# Radio.net
KiCad netlist of a schematic drawn in Altium Designer
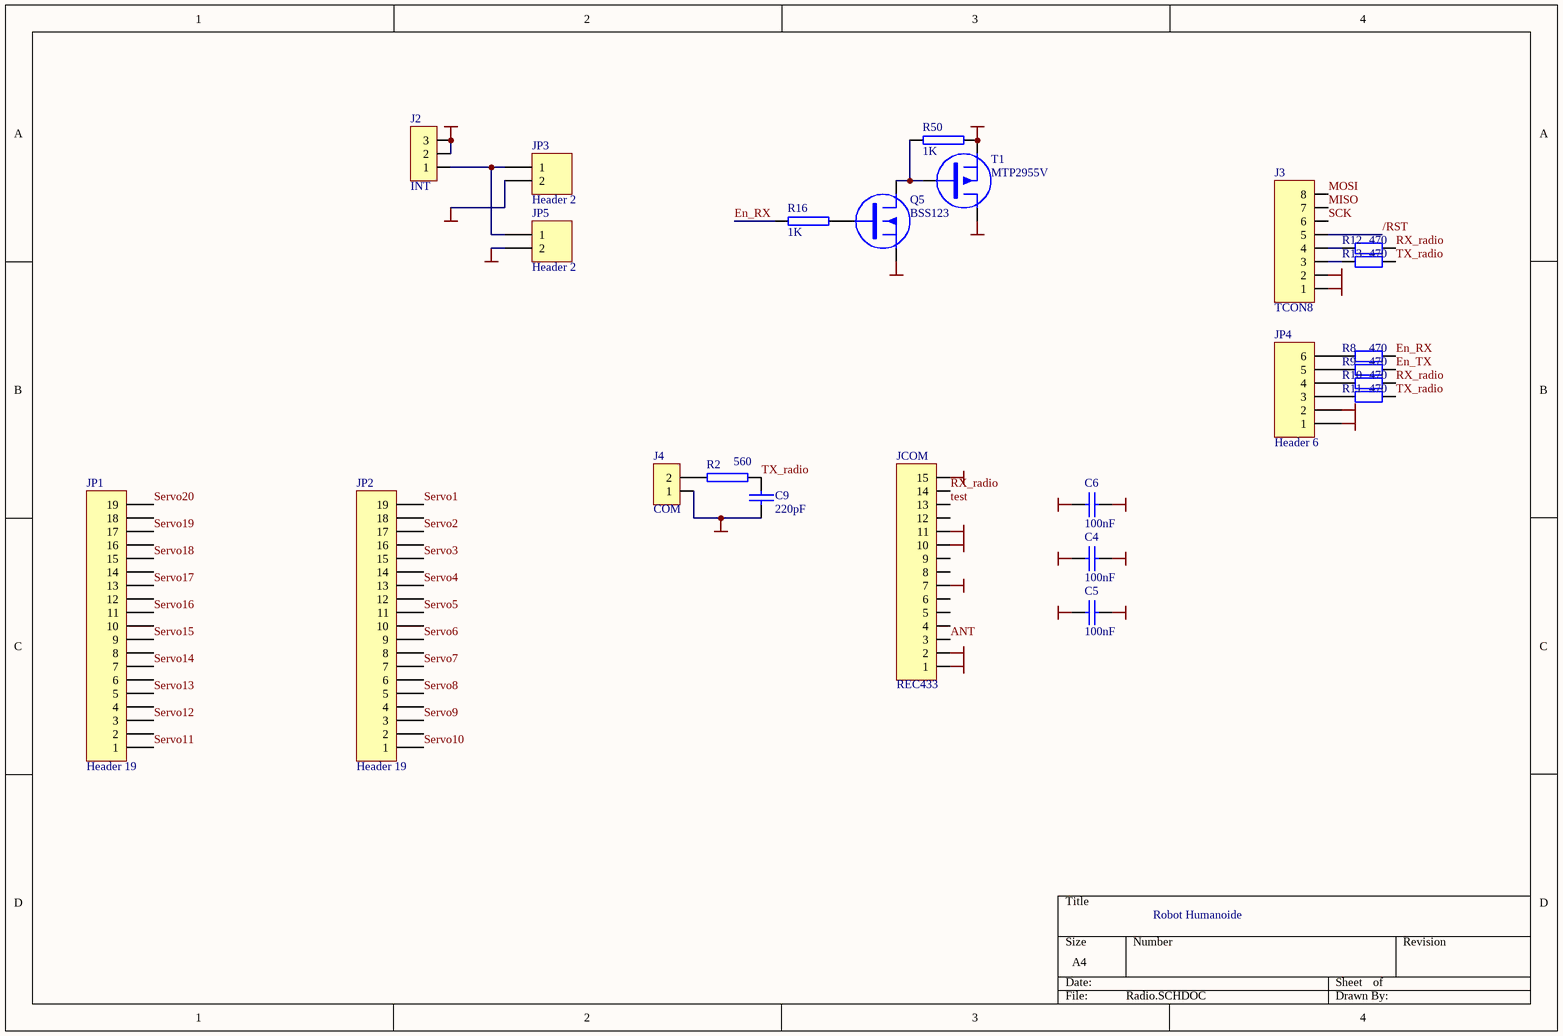
[diagram p0: Radio.SCHDOC]

(export (version "E")
  (design (tool "Eeschema 10.0.6"))
  (components
    (comp (ref "C4")
      (value "100nF")
      (footprint "0805")
      (fields
        (field (name "MANUFACTURER") "Generic Components")
        (field (name "PUBLISHER") "Altium Hobart Technology Centre")
      )
      (libsource (lib "*") (part "CAP"))
    )
    (comp (ref "C5")
      (value "100nF")
      (footprint "0805")
      (fields
        (field (name "MANUFACTURER") "Generic Components")
        (field (name "PUBLISHER") "Altium Hobart Technology Centre")
      )
      (libsource (lib "*") (part "CAP"))
    )
    (comp (ref "C6")
      (value "100nF")
      (footprint "0805")
      (fields
        (field (name "MANUFACTURER") "Generic Components")
        (field (name "PUBLISHER") "Altium Hobart Technology Centre")
      )
      (libsource (lib "*") (part "CAP"))
    )
    (comp (ref "C9")
      (value "220pF")
      (footprint "0805")
      (fields
        (field (name "MANUFACTURER") "Generic Components")
        (field (name "PUBLISHER") "Altium Hobart Technology Centre")
      )
      (libsource (lib "*") (part "CAP"))
    )
    (comp (ref "J2") (value "INT") (footprint "TSIP3") (libsource (lib "*") (part "TCON3")))
    (comp (ref "J3") (value "TCON8") (footprint "TSIP8") (libsource (lib "ROB04") (part "TCON8")))
    (comp (ref "J4") (value "COM") (footprint "CON2") (libsource (lib "*") (part "CON2")))
    (comp (ref "JCOM") (value "REC433") (footprint "TSIP15") (libsource (lib "*") (part "CON15")))
    (comp (ref "JP1")
      (value "Header 19")
      (footprint "HDR1X19")
      (description "Header, 19-Pin")
      (fields (field (name "PUBLISHER") "Altium Limited"))
      (libsource (lib "Miscellaneous Connectors") (part "Header 19"))
    )
    (comp (ref "JP2")
      (value "Header 19")
      (footprint "HDR1X19")
      (description "Header, 19-Pin")
      (fields (field (name "PUBLISHER") "Altium Limited"))
      (libsource (lib "Miscellaneous Connectors") (part "Header 19"))
    )
    (comp (ref "JP3")
      (value "Header 2")
      (footprint "HDR1X2")
      (description "Header, 2-Pin")
      (fields (field (name "PUBLISHER") "Altium Limited"))
      (libsource (lib "Miscellaneous Connectors") (part "Header 2"))
    )
    (comp (ref "JP4")
      (value "Header 6")
      (footprint "TSIP6")
      (description "Header, 6-Pin")
      (fields (field (name "PUBLISHER") "Altium Limited"))
      (libsource (lib "Miscellaneous Connectors") (part "Header 6"))
    )
    (comp (ref "JP5")
      (value "Header 2")
      (footprint "HDR1X2")
      (description "Header, 2-Pin")
      (fields (field (name "PUBLISHER") "Altium Limited"))
      (libsource (lib "Miscellaneous Connectors") (part "Header 2"))
    )
    (comp (ref "Q5") (value "BSS123") (footprint "SOT-23") (libsource (lib "*") (part "BSS123")))
    (comp (ref "R2")
      (value "560")
      (footprint "0805")
      (fields (field (name "PUBLISHER") "*"))
      (libsource (lib "*") (part "RES2"))
    )
    (comp (ref "R8")
      (value "470")
      (footprint "0805")
      (description "Resistor")
      (fields (field (name "Comment") "Res2") (field (name "PUBLISHER") "Altium Limited"))
      (libsource (lib "Miscellaneous Devices") (part "Res2"))
    )
    (comp (ref "R9")
      (value "470")
      (footprint "0805")
      (description "Resistor")
      (fields (field (name "Comment") "Res2") (field (name "PUBLISHER") "Altium Limited"))
      (libsource (lib "Miscellaneous Devices") (part "Res2"))
    )
    (comp (ref "R10")
      (value "470")
      (footprint "0805")
      (description "Resistor")
      (fields (field (name "Comment") "Res2") (field (name "PUBLISHER") "Altium Limited"))
      (libsource (lib "Miscellaneous Devices") (part "Res2"))
    )
    (comp (ref "R11")
      (value "470")
      (footprint "0805")
      (description "Resistor")
      (fields (field (name "Comment") "Res2") (field (name "PUBLISHER") "Altium Limited"))
      (libsource (lib "Miscellaneous Devices") (part "Res2"))
    )
    (comp (ref "R12")
      (value "470")
      (footprint "0805")
      (description "Resistor")
      (fields (field (name "Comment") "Res2") (field (name "PUBLISHER") "Altium Limited"))
      (libsource (lib "Miscellaneous Devices") (part "Res2"))
    )
    (comp (ref "R13")
      (value "470")
      (footprint "0805")
      (description "Resistor")
      (fields (field (name "Comment") "Res2") (field (name "PUBLISHER") "Altium Limited"))
      (libsource (lib "Miscellaneous Devices") (part "Res2"))
    )
    (comp (ref "R16") (value "1K") (footprint "0805") (libsource (lib "*") (part "TRESIST")))
    (comp (ref "R50") (value "1K") (footprint "0805") (libsource (lib "*") (part "TRESIST")))
    (comp (ref "T1") (value "MTP2955V") (footprint "TTO220C") (libsource (lib "*") (part "MTP2955V")))
  )
  (nets
    (net (code "1") (name "/ANT") (class "Default")
      (node (ref "JCOM") (pin "3") (pinfunction "3_3") (pintype "passive"))
    )
    (net (code "2") (name "/En_RX") (class "Default")
      (node (ref "R16") (pin "1") (pintype "passive"))
      (node (ref "R8") (pin "2") (pinfunction "2_2") (pintype "passive"))
    )
    (net (code "3") (name "/En_TX") (class "Default")
      (node (ref "R9") (pin "2") (pinfunction "2_2") (pintype "passive"))
    )
    (net (code "4") (name "/MISO") (class "Default")
      (node (ref "J3") (pin "7") (pinfunction "7_7") (pintype "passive"))
    )
    (net (code "5") (name "/MOSI") (class "Default")
      (node (ref "J3") (pin "8") (pinfunction "8_8") (pintype "passive"))
    )
    (net (code "6") (name "/RX_radio") (class "Default")
      (node (ref "JCOM") (pin "14") (pinfunction "14_14") (pintype "passive"))
      (node (ref "R10") (pin "2") (pinfunction "2_2") (pintype "passive"))
      (node (ref "R12") (pin "2") (pinfunction "2_2") (pintype "passive"))
    )
    (net (code "7") (name "/SCK") (class "Default")
      (node (ref "J3") (pin "6") (pinfunction "6_6") (pintype "passive"))
    )
    (net (code "8") (name "/Servo1") (class "Default")
      (node (ref "JP2") (pin "19") (pinfunction "19_19") (pintype "passive"))
    )
    (net (code "9") (name "/Servo2") (class "Default")
      (node (ref "JP2") (pin "17") (pinfunction "17_17") (pintype "passive"))
    )
    (net (code "10") (name "/Servo3") (class "Default")
      (node (ref "JP2") (pin "15") (pinfunction "15_15") (pintype "passive"))
    )
    (net (code "11") (name "/Servo4") (class "Default")
      (node (ref "JP2") (pin "13") (pinfunction "13_13") (pintype "passive"))
    )
    (net (code "12") (name "/Servo5") (class "Default")
      (node (ref "JP2") (pin "11") (pinfunction "11_11") (pintype "passive"))
    )
    (net (code "13") (name "/Servo6") (class "Default")
      (node (ref "JP2") (pin "9") (pinfunction "9_9") (pintype "passive"))
    )
    (net (code "14") (name "/Servo7") (class "Default")
      (node (ref "JP2") (pin "7") (pinfunction "7_7") (pintype "passive"))
    )
    (net (code "15") (name "/Servo8") (class "Default")
      (node (ref "JP2") (pin "5") (pinfunction "5_5") (pintype "passive"))
    )
    (net (code "16") (name "/Servo9") (class "Default")
      (node (ref "JP2") (pin "3") (pinfunction "3_3") (pintype "passive"))
    )
    (net (code "17") (name "/Servo10") (class "Default")
      (node (ref "JP2") (pin "1") (pinfunction "1_1") (pintype "passive"))
    )
    (net (code "18") (name "/Servo11") (class "Default")
      (node (ref "JP1") (pin "1") (pinfunction "1_1") (pintype "passive"))
    )
    (net (code "19") (name "/Servo12") (class "Default")
      (node (ref "JP1") (pin "3") (pinfunction "3_3") (pintype "passive"))
    )
    (net (code "20") (name "/Servo13") (class "Default")
      (node (ref "JP1") (pin "5") (pinfunction "5_5") (pintype "passive"))
    )
    (net (code "21") (name "/Servo14") (class "Default")
      (node (ref "JP1") (pin "7") (pinfunction "7_7") (pintype "passive"))
    )
    (net (code "22") (name "/Servo15") (class "Default")
      (node (ref "JP1") (pin "9") (pinfunction "9_9") (pintype "passive"))
    )
    (net (code "23") (name "/Servo16") (class "Default")
      (node (ref "JP1") (pin "11") (pinfunction "11_11") (pintype "passive"))
    )
    (net (code "24") (name "/Servo17") (class "Default")
      (node (ref "JP1") (pin "13") (pinfunction "13_13") (pintype "passive"))
    )
    (net (code "25") (name "/Servo18") (class "Default")
      (node (ref "JP1") (pin "15") (pinfunction "15_15") (pintype "passive"))
    )
    (net (code "26") (name "/Servo19") (class "Default")
      (node (ref "JP1") (pin "17") (pinfunction "17_17") (pintype "passive"))
    )
    (net (code "27") (name "/Servo20") (class "Default")
      (node (ref "JP1") (pin "19") (pinfunction "19_19") (pintype "passive"))
    )
    (net (code "28") (name "/TX_radio") (class "Default")
      (node (ref "C9") (pin "2") (pintype "passive"))
      (node (ref "R11") (pin "2") (pinfunction "2_2") (pintype "passive"))
      (node (ref "R13") (pin "2") (pinfunction "2_2") (pintype "passive"))
      (node (ref "R2") (pin "2") (pintype "passive"))
    )
    (net (code "29") (name "/test") (class "Default")
      (node (ref "JCOM") (pin "13") (pinfunction "13_13") (pintype "passive"))
    )
    (net (code "30") (name "/{slash}RST") (class "Default")
      (node (ref "J3") (pin "5") (pinfunction "5_5") (pintype "passive"))
    )
    (net (code "31") (name "5V") (class "Default")
      (node (ref "C4") (pin "2") (pintype "passive"))
      (node (ref "C5") (pin "2") (pintype "passive"))
      (node (ref "C6") (pin "2") (pintype "passive"))
      (node (ref "J3") (pin "1") (pinfunction "1_1") (pintype "passive"))
      (node (ref "JCOM") (pin "1") (pinfunction "1_1") (pintype "passive"))
      (node (ref "JCOM") (pin "10") (pinfunction "10_10") (pintype "passive"))
      (node (ref "JCOM") (pin "15") (pinfunction "15_15") (pintype "passive"))
      (node (ref "JP4") (pin "1") (pinfunction "1_1") (pintype "passive"))
      (node (ref "T1") (pin "2") (pinfunction "C_2") (pintype "passive"))
    )
    (net (code "32") (name "GND") (class "Default")
      (node (ref "C4") (pin "1") (pintype "passive"))
      (node (ref "C5") (pin "1") (pintype "passive"))
      (node (ref "C6") (pin "1") (pintype "passive"))
      (node (ref "C9") (pin "1") (pintype "passive"))
      (node (ref "J3") (pin "2") (pinfunction "2_2") (pintype "passive"))
      (node (ref "J4") (pin "1") (pinfunction "1_1") (pintype "passive"))
      (node (ref "JCOM") (pin "11") (pinfunction "11_11") (pintype "passive"))
      (node (ref "JCOM") (pin "2") (pinfunction "2_2") (pintype "passive"))
      (node (ref "JCOM") (pin "7") (pinfunction "7_7") (pintype "passive"))
      (node (ref "JP3") (pin "2") (pinfunction "2_2") (pintype "passive"))
      (node (ref "JP4") (pin "2") (pinfunction "2_2") (pintype "passive"))
      (node (ref "JP5") (pin "2") (pinfunction "2_2") (pintype "passive"))
      (node (ref "Q5") (pin "2") (pinfunction "C_2") (pintype "passive"))
    )
    (net (code "33") (name "Net-(J2-Pad1)") (class "Default")
      (node (ref "J2") (pin "1") (pinfunction "1_1") (pintype "passive"))
      (node (ref "JP3") (pin "1") (pinfunction "1_1") (pintype "passive"))
      (node (ref "JP5") (pin "1") (pinfunction "1_1") (pintype "passive"))
    )
    (net (code "34") (name "Net-(J3-Pad3)") (class "Default")
      (node (ref "J3") (pin "3") (pinfunction "3_3") (pintype "passive"))
      (node (ref "R13") (pin "1") (pinfunction "1_1") (pintype "passive"))
    )
    (net (code "35") (name "Net-(J3-Pad4)") (class "Default")
      (node (ref "J3") (pin "4") (pinfunction "4_4") (pintype "passive"))
      (node (ref "R12") (pin "1") (pinfunction "1_1") (pintype "passive"))
    )
    (net (code "36") (name "Net-(J4-Pad2)") (class "Default")
      (node (ref "J4") (pin "2") (pinfunction "2_2") (pintype "passive"))
      (node (ref "R2") (pin "1") (pintype "passive"))
    )
    (net (code "37") (name "Net-(JP4-Pad3)") (class "Default")
      (node (ref "JP4") (pin "3") (pinfunction "3_3") (pintype "passive"))
      (node (ref "R11") (pin "1") (pinfunction "1_1") (pintype "passive"))
    )
    (net (code "38") (name "Net-(JP4-Pad4)") (class "Default")
      (node (ref "JP4") (pin "4") (pinfunction "4_4") (pintype "passive"))
      (node (ref "R10") (pin "1") (pinfunction "1_1") (pintype "passive"))
    )
    (net (code "39") (name "Net-(JP4-Pad5)") (class "Default")
      (node (ref "JP4") (pin "5") (pinfunction "5_5") (pintype "passive"))
      (node (ref "R9") (pin "1") (pinfunction "1_1") (pintype "passive"))
    )
    (net (code "40") (name "Net-(JP4-Pad6)") (class "Default")
      (node (ref "JP4") (pin "6") (pinfunction "6_6") (pintype "passive"))
      (node (ref "R8") (pin "1") (pinfunction "1_1") (pintype "passive"))
    )
    (net (code "41") (name "Net-(Q5-B)") (class "Default")
      (node (ref "Q5") (pin "1") (pinfunction "B_1") (pintype "passive"))
      (node (ref "R16") (pin "2") (pintype "passive"))
    )
    (net (code "42") (name "Net-(Q5-E)") (class "Default")
      (node (ref "Q5") (pin "3") (pinfunction "E_3") (pintype "passive"))
      (node (ref "R50") (pin "1") (pintype "passive"))
      (node (ref "T1") (pin "1") (pinfunction "B_1") (pintype "passive"))
    )
    (net (code "43") (name "VCC") (class "Default")
      (node (ref "J2") (pin "2") (pinfunction "2_2") (pintype "passive"))
      (node (ref "J2") (pin "3") (pinfunction "3_3") (pintype "passive"))
      (node (ref "R50") (pin "2") (pintype "passive"))
      (node (ref "T1") (pin "3") (pinfunction "E_3") (pintype "passive"))
    )
    (net (code "44") (name "unconnected-(JCOM-Pad4)") (class "Default")
      (node (ref "JCOM") (pin "4") (pinfunction "4_4") (pintype "passive"))
    )
    (net (code "45") (name "unconnected-(JCOM-Pad5)") (class "Default")
      (node (ref "JCOM") (pin "5") (pinfunction "5_5") (pintype "passive"))
    )
    (net (code "46") (name "unconnected-(JCOM-Pad6)") (class "Default")
      (node (ref "JCOM") (pin "6") (pinfunction "6_6") (pintype "passive"))
    )
    (net (code "47") (name "unconnected-(JCOM-Pad8)") (class "Default")
      (node (ref "JCOM") (pin "8") (pinfunction "8_8") (pintype "passive"))
    )
    (net (code "48") (name "unconnected-(JCOM-Pad9)") (class "Default")
      (node (ref "JCOM") (pin "9") (pinfunction "9_9") (pintype "passive"))
    )
    (net (code "49") (name "unconnected-(JCOM-Pad12)") (class "Default")
      (node (ref "JCOM") (pin "12") (pinfunction "12_12") (pintype "passive"))
    )
    (net (code "50") (name "unconnected-(JP1-Pad2)") (class "Default")
      (node (ref "JP1") (pin "2") (pinfunction "2_2") (pintype "passive"))
    )
    (net (code "51") (name "unconnected-(JP1-Pad4)") (class "Default")
      (node (ref "JP1") (pin "4") (pinfunction "4_4") (pintype "passive"))
    )
    (net (code "52") (name "unconnected-(JP1-Pad6)") (class "Default")
      (node (ref "JP1") (pin "6") (pinfunction "6_6") (pintype "passive"))
    )
    (net (code "53") (name "unconnected-(JP1-Pad8)") (class "Default")
      (node (ref "JP1") (pin "8") (pinfunction "8_8") (pintype "passive"))
    )
    (net (code "54") (name "unconnected-(JP1-Pad10)") (class "Default")
      (node (ref "JP1") (pin "10") (pinfunction "10_10") (pintype "passive"))
    )
    (net (code "55") (name "unconnected-(JP1-Pad12)") (class "Default")
      (node (ref "JP1") (pin "12") (pinfunction "12_12") (pintype "passive"))
    )
    (net (code "56") (name "unconnected-(JP1-Pad14)") (class "Default")
      (node (ref "JP1") (pin "14") (pinfunction "14_14") (pintype "passive"))
    )
    (net (code "57") (name "unconnected-(JP1-Pad16)") (class "Default")
      (node (ref "JP1") (pin "16") (pinfunction "16_16") (pintype "passive"))
    )
    (net (code "58") (name "unconnected-(JP1-Pad18)") (class "Default")
      (node (ref "JP1") (pin "18") (pinfunction "18_18") (pintype "passive"))
    )
    (net (code "59") (name "unconnected-(JP2-Pad2)") (class "Default")
      (node (ref "JP2") (pin "2") (pinfunction "2_2") (pintype "passive"))
    )
    (net (code "60") (name "unconnected-(JP2-Pad4)") (class "Default")
      (node (ref "JP2") (pin "4") (pinfunction "4_4") (pintype "passive"))
    )
    (net (code "61") (name "unconnected-(JP2-Pad6)") (class "Default")
      (node (ref "JP2") (pin "6") (pinfunction "6_6") (pintype "passive"))
    )
    (net (code "62") (name "unconnected-(JP2-Pad8)") (class "Default")
      (node (ref "JP2") (pin "8") (pinfunction "8_8") (pintype "passive"))
    )
    (net (code "63") (name "unconnected-(JP2-Pad10)") (class "Default")
      (node (ref "JP2") (pin "10") (pinfunction "10_10") (pintype "passive"))
    )
    (net (code "64") (name "unconnected-(JP2-Pad12)") (class "Default")
      (node (ref "JP2") (pin "12") (pinfunction "12_12") (pintype "passive"))
    )
    (net (code "65") (name "unconnected-(JP2-Pad14)") (class "Default")
      (node (ref "JP2") (pin "14") (pinfunction "14_14") (pintype "passive"))
    )
    (net (code "66") (name "unconnected-(JP2-Pad16)") (class "Default")
      (node (ref "JP2") (pin "16") (pinfunction "16_16") (pintype "passive"))
    )
    (net (code "67") (name "unconnected-(JP2-Pad18)") (class "Default")
      (node (ref "JP2") (pin "18") (pinfunction "18_18") (pintype "passive"))
    )
  )
)
